# ETHERNET_STM32.net
KiCad netlist of a schematic drawn in Altium Designer
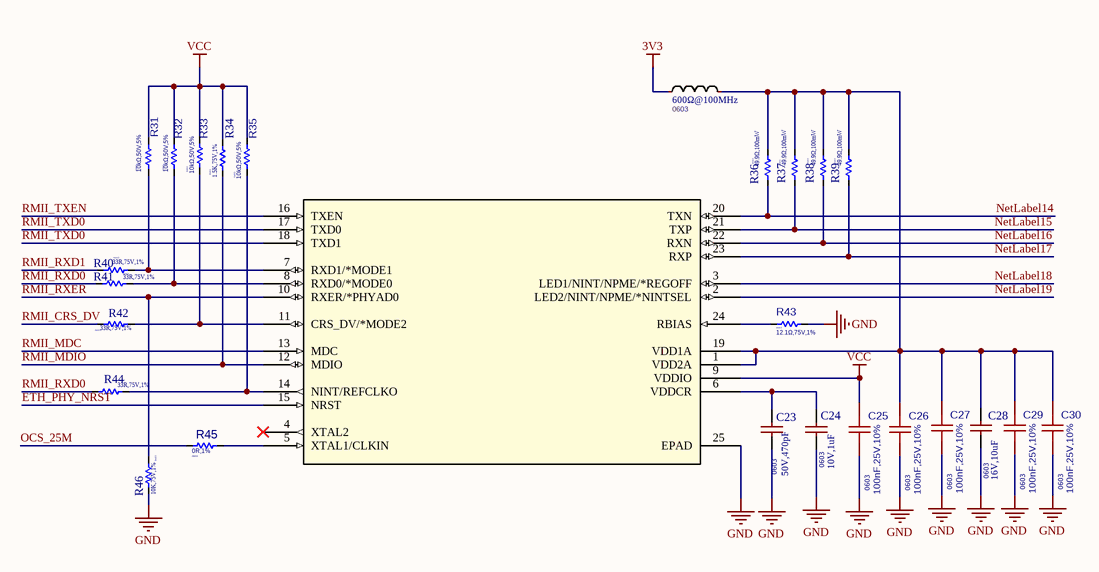
[diagram p0: ETHERNET_STM32.SchDoc]

(export (version "E")
  (design (tool "Eeschema 10.0.6"))
  (components
    (comp (ref "C23")
      (value "50V,470pF")
      (footprint "c-0603")
      (description "50V 470pF X7R ±10% 0603 Multilayer Ceramic Capacitors MLCC - SMD/SMT ROHS")
      (fields
        (field (name "MANUFACTURER") "FH")
        (field (name "MPN") "CL10B471KB8NNNC")
        (field (name "PACKAGE") "0603")
      )
      (libsource (lib "RCL") (part "CL10B471KB8NNNC"))
    )
    (comp (ref "C24")
      (value "10V,1uF")
      (footprint "CAPC1608X90N")
      (description "10V 1uF X5R ±10% 0603 Multilayer Ceramic Capacitors MLCC - SMD/SMT ROHS")
      (fields
        (field (name "MANUFACTURER") "SAMSUNG")
        (field (name "MPN") "CL10A105KP8NNNC")
        (field (name "PACKAGE") "0603")
      )
      (libsource (lib "RCL") (part "CL10A105KP8NNNC"))
    )
    (comp (ref "C25")
      (value "100nF,25V,10%")
      (footprint "C0603")
      (description "25V 100nF X7R ±10% 0603 Multilayer Ceramic Capacitors MLCC - SMD/SMT ROHS")
      (fields
        (field (name "MANUFACTURER") "SAMSUNG")
        (field (name "MPN") "CL10B104KA8NNNC")
        (field (name "PACKAGE") "0603")
      )
      (libsource (lib "RCL") (part "CL10B104KA8NNNC"))
    )
    (comp (ref "C26")
      (value "100nF,25V,10%")
      (footprint "C0603")
      (description "25V 100nF X7R ±10% 0603 Multilayer Ceramic Capacitors MLCC - SMD/SMT ROHS")
      (fields
        (field (name "MANUFACTURER") "SAMSUNG")
        (field (name "MPN") "CL10B104KA8NNNC")
        (field (name "PACKAGE") "0603")
      )
      (libsource (lib "RCL") (part "CL10B104KA8NNNC"))
    )
    (comp (ref "C27")
      (value "100nF,25V,10%")
      (footprint "C0603")
      (description "25V 100nF X7R ±10% 0603 Multilayer Ceramic Capacitors MLCC - SMD/SMT ROHS")
      (fields
        (field (name "MANUFACTURER") "SAMSUNG")
        (field (name "MPN") "CL10B104KA8NNNC")
        (field (name "PACKAGE") "0603")
      )
      (libsource (lib "RCL") (part "CL10B104KA8NNNC"))
    )
    (comp (ref "C28")
      (value "16V,10uF")
      (footprint "CAPC1608X90N")
      (description "16V 10uF Y5V ±20% 0603 Multilayer Ceramic Capacitors MLCC - SMD/SMT ROHS")
      (fields
        (field (name "MANUFACTURER") "KEMET")
        (field (name "MPN") "CC0603KRX7R9BB104")
        (field (name "PACKAGE") "0603")
      )
      (libsource (lib "RCL") (part "0603F106M160NT"))
    )
    (comp (ref "C29")
      (value "100nF,25V,10%")
      (footprint "C0603")
      (description "25V 100nF X7R ±10% 0603 Multilayer Ceramic Capacitors MLCC - SMD/SMT ROHS")
      (fields
        (field (name "MANUFACTURER") "SAMSUNG")
        (field (name "MPN") "CL10B104KA8NNNC")
        (field (name "PACKAGE") "0603")
      )
      (libsource (lib "RCL") (part "CL10B104KA8NNNC"))
    )
    (comp (ref "C30")
      (value "100nF,25V,10%")
      (footprint "C0603")
      (description "25V 100nF X7R ±10% 0603 Multilayer Ceramic Capacitors MLCC - SMD/SMT ROHS")
      (fields
        (field (name "MANUFACTURER") "SAMSUNG")
        (field (name "MPN") "CL10B104KA8NNNC")
        (field (name "PACKAGE") "0603")
      )
      (libsource (lib "RCL") (part "CL10B104KA8NNNC"))
    )
    (comp (ref "R31")
      (value "10kΩ,50V,5%")
      (footprint "R0402")
      (description "62.5mW Thick Film Resistors 50V ±100ppm/℃ ±5% 10kΩ 0402 Chip Resistor - Surface Mount ROHS")
      (fields
        (field (name "MANUFACTURER") "YAGEO")
        (field (name "MPN") "RC0402JR-0710KL")
        (field (name "PACKAGE") "0402")
      )
      (libsource (lib "RCL") (part "RC0402JR-0710KL"))
    )
    (comp (ref "R32")
      (value "10kΩ,50V,5%")
      (footprint "R0402")
      (description "62.5mW Thick Film Resistors 50V ±100ppm/℃ ±5% 10kΩ 0402 Chip Resistor - Surface Mount ROHS")
      (fields
        (field (name "MANUFACTURER") "YAGEO")
        (field (name "MPN") "RC0402JR-0710KL")
        (field (name "PACKAGE") "0402")
      )
      (libsource (lib "RCL") (part "RC0402JR-0710KL"))
    )
    (comp (ref "R33")
      (value "10kΩ,50V,5%")
      (footprint "R0402")
      (description "62.5mW Thick Film Resistors 50V ±100ppm/℃ ±5% 10kΩ 0402 Chip Resistor - Surface Mount ROHS")
      (fields
        (field (name "MANUFACTURER") "YAGEO")
        (field (name "MPN") "RC0402JR-0710KL")
        (field (name "PACKAGE") "0402")
      )
      (libsource (lib "RCL") (part "RC0402JR-0710KL"))
    )
    (comp (ref "R34")
      (value "1.5K,75V,1%")
      (footprint "R0603")
      (description "100mW Thick Film Resistors 75V ±100ppm/℃ ±1% 1.5kΩ 0603 Chip Resistor - Surface Mount ROHS")
      (fields
        (field (name "MANUFACTURER") "Yageo")
        (field (name "MPN") "RC0603FR-071K5L")
        (field (name "PACKAGE") "0603")
      )
      (libsource (lib "RCL") (part "RC0603FR-071K5L"))
    )
    (comp (ref "R35")
      (value "10kΩ,50V,5%")
      (footprint "R0402")
      (description "62.5mW Thick Film Resistors 50V ±100ppm/℃ ±5% 10kΩ 0402 Chip Resistor - Surface Mount ROHS")
      (fields
        (field (name "MANUFACTURER") "YAGEO")
        (field (name "MPN") "RC0402JR-0710KL")
        (field (name "PACKAGE") "0402")
      )
      (libsource (lib "RCL") (part "RC0402JR-0710KL"))
    )
    (comp (ref "R36")
      (value "49.9Ω,100mW")
      (footprint "R0603")
      (description "100mW Thick Film Resistors ±100ppm/℃ ±1% 49.9Ω 0603 Chip Resistor - Surface Mount ROHS")
      (fields
        (field (name "MANUFACTURER") "Panasonic")
        (field (name "MPN") "ERJ-3EKF49R9V")
        (field (name "PACKAGE") "0603")
      )
      (libsource (lib "RCL") (part "ERJ-3EKF49R9V"))
    )
    (comp (ref "R37")
      (value "49.9Ω,100mW")
      (footprint "R0603")
      (description "100mW Thick Film Resistors ±100ppm/℃ ±1% 49.9Ω 0603 Chip Resistor - Surface Mount ROHS")
      (fields
        (field (name "MANUFACTURER") "Panasonic")
        (field (name "MPN") "ERJ-3EKF49R9V")
        (field (name "PACKAGE") "0603")
      )
      (libsource (lib "RCL") (part "ERJ-3EKF49R9V"))
    )
    (comp (ref "R38")
      (value "49.9Ω,100mW")
      (footprint "R0603")
      (description "100mW Thick Film Resistors ±100ppm/℃ ±1% 49.9Ω 0603 Chip Resistor - Surface Mount ROHS")
      (fields
        (field (name "MANUFACTURER") "Panasonic")
        (field (name "MPN") "ERJ-3EKF49R9V")
        (field (name "PACKAGE") "0603")
      )
      (libsource (lib "RCL") (part "ERJ-3EKF49R9V"))
    )
    (comp (ref "R39")
      (value "49.9Ω,100mW")
      (footprint "R0603")
      (description "100mW Thick Film Resistors ±100ppm/℃ ±1% 49.9Ω 0603 Chip Resistor - Surface Mount ROHS")
      (fields
        (field (name "MANUFACTURER") "Panasonic")
        (field (name "MPN") "ERJ-3EKF49R9V")
        (field (name "PACKAGE") "0603")
      )
      (libsource (lib "RCL") (part "ERJ-3EKF49R9V"))
    )
    (comp (ref "R40")
      (value "33R,75V,1%")
      (footprint "R0603")
      (description "100mW Thick Film Resistors 75V ±100ppm/℃ ±1% 270Ω 0603 Chip Resistor - Surface Mount ROHS")
      (fields
        (field (name "MANUFACTURER") "Yageo")
        (field (name "MPN") "RC0603FR-0733RL")
        (field (name "PACKAGE") "0603")
      )
      (libsource (lib "RCL") (part "RC0603FR-0733RL"))
    )
    (comp (ref "R41")
      (value "33R,75V,1%")
      (footprint "R0603")
      (description "100mW Thick Film Resistors 75V ±100ppm/℃ ±1% 270Ω 0603 Chip Resistor - Surface Mount ROHS")
      (fields
        (field (name "MANUFACTURER") "Yageo")
        (field (name "MPN") "RC0603FR-0733RL")
        (field (name "PACKAGE") "0603")
      )
      (libsource (lib "RCL") (part "RC0603FR-0733RL"))
    )
    (comp (ref "R42")
      (value "33R,75V,1%")
      (footprint "R0603")
      (description "100mW Thick Film Resistors 75V ±100ppm/℃ ±1% 270Ω 0603 Chip Resistor - Surface Mount ROHS")
      (fields
        (field (name "MANUFACTURER") "Yageo")
        (field (name "MPN") "RC0603FR-0733RL")
        (field (name "PACKAGE") "0603")
      )
      (libsource (lib "RCL") (part "RC0603FR-0733RL"))
    )
    (comp (ref "R43")
      (value "12.1Ω,75V,1%")
      (footprint "R0603")
      (description "100mW Thick Film Resistors 75V ±100ppm/℃ ±1% 12.1kΩ 0603 Chip Resistor - Surface Mount ROHS")
      (fields
        (field (name "MPN") "RC0603FR-0712K1L")
        (field (name "MANUFACTURER") "YAGEO")
        (field (name "PACKAGE") "0603")
      )
      (libsource (lib "RCL") (part "RC0603FR-0712K1L"))
    )
    (comp (ref "R44")
      (value "33R,75V,1%")
      (footprint "R0603")
      (description "100mW Thick Film Resistors 75V ±100ppm/℃ ±1% 270Ω 0603 Chip Resistor - Surface Mount ROHS")
      (fields
        (field (name "MANUFACTURER") "Yageo")
        (field (name "MPN") "RC0603FR-0733RL")
        (field (name "PACKAGE") "0603")
      )
      (libsource (lib "RCL") (part "RC0603FR-0733RL"))
    )
    (comp (ref "R45")
      (value "0R,1%")
      (footprint "R0603")
      (description "RES SMD 0 OHM JUMPER 1/10W 0603")
      (fields
        (field (name "MANUFACTURER") "YAGEO")
        (field (name "MPN") "AC0603FR-070RL")
        (field (name "PACKAGE") "0603")
      )
      (libsource (lib "RCL") (part "AC0603FR-070RL"))
    )
    (comp (ref "R46")
      (value "10K,75V,1%")
      (footprint "R0603")
      (description "100mW Thick Film Resistors ±100ppm/℃ ±1% 10kΩ 0603 Chip Resistor - Surface Mount ROHS")
      (fields
        (field (name "MPN") "0603WAF1002T5E")
        (field (name "MANUFACTURER") "UNI-ROYAL(Uniroyal Elec)")
        (field (name "PACKAGE") "0603")
      )
      (libsource (lib "RCL") (part "0603WAF1002T5E"))
    )
    (comp (ref "U4")
      (value "600Ω@100MHz")
      (footprint "L-0603")
      (description "380mΩ ±25% 600Ω@100MHz 0603 Ferrite Beads ROHS")
      (fields
        (field (name "MANUFACTURER") "muRata")
        (field (name "MPN") "BLM18AG601SN1D")
        (field (name "PACKAGE") "0603")
      )
      (libsource (lib "RCL") (part "BLM18AG601SN1D"))
    )
    (comp (ref "U5")
      (value "LAN8742A-CZ-TR")
      (footprint "QFN-24-EP(4x4)")
      (description "QFN-24-EP(4x4) Ethernet ICs ROHS")
      (fields (field (name "MANUFACTURER") "MICROCHIP(美国微芯)"))
      (libsource (lib "IC") (part "LAN8742A-CZ-TR"))
    )
  )
  (nets
    (net (code "1") (name "/ETH_PHY_NRST") (class "Default")
      (node (ref "U5") (pin "15") (pinfunction "NRST_15") (pintype "input"))
    )
    (net (code "2") (name "/NetLabel14") (class "Default")
      (node (ref "R36") (pin "1") (pinfunction "1_1") (pintype "passive"))
      (node (ref "U5") (pin "20") (pinfunction "TXN_20") (pintype "bidirectional"))
    )
    (net (code "3") (name "/NetLabel15") (class "Default")
      (node (ref "R37") (pin "1") (pinfunction "1_1") (pintype "passive"))
      (node (ref "U5") (pin "21") (pinfunction "TXP_21") (pintype "bidirectional"))
    )
    (net (code "4") (name "/NetLabel16") (class "Default")
      (node (ref "R38") (pin "1") (pinfunction "1_1") (pintype "passive"))
      (node (ref "U5") (pin "22") (pinfunction "RXN_22") (pintype "bidirectional"))
    )
    (net (code "5") (name "/NetLabel17") (class "Default")
      (node (ref "R39") (pin "1") (pinfunction "1_1") (pintype "passive"))
      (node (ref "U5") (pin "23") (pinfunction "RXP_23") (pintype "bidirectional"))
    )
    (net (code "6") (name "/NetLabel18") (class "Default")
      (node (ref "U5") (pin "3") (pinfunction "LED1/NINT/NPME/*REGOFF_3") (pintype "bidirectional"))
    )
    (net (code "7") (name "/NetLabel19") (class "Default")
      (node (ref "U5") (pin "2") (pinfunction "LED2/NINT/NPME/*NINTSEL_2") (pintype "bidirectional"))
    )
    (net (code "8") (name "/OCS_25M") (class "Default")
      (node (ref "R45") (pin "1") (pinfunction "1_1") (pintype "passive"))
    )
    (net (code "9") (name "/RMII_CRS_DV") (class "Default")
      (node (ref "R42") (pin "1") (pinfunction "1_1") (pintype "passive"))
    )
    (net (code "10") (name "/RMII_MDC") (class "Default")
      (node (ref "U5") (pin "13") (pinfunction "MDC_13") (pintype "input"))
    )
    (net (code "11") (name "/RMII_MDIO") (class "Default")
      (node (ref "R34") (pin "1") (pinfunction "1_1") (pintype "passive"))
      (node (ref "U5") (pin "12") (pinfunction "MDIO_12") (pintype "bidirectional"))
    )
    (net (code "12") (name "/RMII_RXD0") (class "Default")
      (node (ref "R41") (pin "1") (pinfunction "1_1") (pintype "passive"))
      (node (ref "R44") (pin "1") (pinfunction "1_1") (pintype "passive"))
    )
    (net (code "13") (name "/RMII_RXD1") (class "Default")
      (node (ref "R40") (pin "1") (pinfunction "1_1") (pintype "passive"))
    )
    (net (code "14") (name "/RMII_RXER") (class "Default")
      (node (ref "R46") (pin "2") (pinfunction "2_2") (pintype "passive"))
      (node (ref "U5") (pin "10") (pinfunction "RXER/*PHYAD0_10") (pintype "bidirectional"))
    )
    (net (code "15") (name "/RMII_TXD0") (class "Default")
      (node (ref "U5") (pin "17") (pinfunction "TXD0_17") (pintype "input"))
      (node (ref "U5") (pin "18") (pinfunction "TXD1_18") (pintype "input"))
    )
    (net (code "16") (name "/RMII_TXEN") (class "Default")
      (node (ref "U5") (pin "16") (pinfunction "TXEN_16") (pintype "input"))
    )
    (net (code "17") (name "3V3") (class "Default")
      (node (ref "U4") (pin "1") (pinfunction "1_1") (pintype "passive"))
    )
    (net (code "18") (name "GND") (class "Default")
      (node (ref "C23") (pin "1") (pinfunction "1_1") (pintype "passive"))
      (node (ref "C24") (pin "1") (pinfunction "1_1") (pintype "passive"))
      (node (ref "C25") (pin "1") (pinfunction "1_1") (pintype "passive"))
      (node (ref "C26") (pin "1") (pinfunction "1_1") (pintype "passive"))
      (node (ref "C27") (pin "1") (pinfunction "1_1") (pintype "passive"))
      (node (ref "C28") (pin "1") (pinfunction "1_1") (pintype "passive"))
      (node (ref "C29") (pin "1") (pinfunction "1_1") (pintype "passive"))
      (node (ref "C30") (pin "1") (pinfunction "1_1") (pintype "passive"))
      (node (ref "R43") (pin "2") (pinfunction "2_2") (pintype "passive"))
      (node (ref "R46") (pin "1") (pinfunction "1_1") (pintype "passive"))
      (node (ref "U5") (pin "25") (pinfunction "EPAD_25") (pintype "passive"))
    )
    (net (code "19") (name "Net-(U5-CRS_DV{slash}*MODE2)") (class "Default")
      (node (ref "R33") (pin "1") (pinfunction "1_1") (pintype "passive"))
      (node (ref "R42") (pin "2") (pinfunction "2_2") (pintype "passive"))
      (node (ref "U5") (pin "11") (pinfunction "CRS_DV/*MODE2_11") (pintype "bidirectional"))
    )
    (net (code "20") (name "Net-(U5-NINT{slash}REFCLKO)") (class "Default")
      (node (ref "R35") (pin "1") (pinfunction "1_1") (pintype "passive"))
      (node (ref "R44") (pin "2") (pinfunction "2_2") (pintype "passive"))
      (node (ref "U5") (pin "14") (pinfunction "NINT/REFCLKO_14") (pintype "output"))
    )
    (net (code "21") (name "Net-(U5-RBIAS)") (class "Default")
      (node (ref "R43") (pin "1") (pinfunction "1_1") (pintype "passive"))
      (node (ref "U5") (pin "24") (pinfunction "RBIAS_24") (pintype "input"))
    )
    (net (code "22") (name "Net-(U5-RXD0{slash}*MODE0)") (class "Default")
      (node (ref "R32") (pin "1") (pinfunction "1_1") (pintype "passive"))
      (node (ref "R41") (pin "2") (pinfunction "2_2") (pintype "passive"))
      (node (ref "U5") (pin "8") (pinfunction "RXD0/*MODE0_8") (pintype "bidirectional"))
    )
    (net (code "23") (name "Net-(U5-RXD1{slash}*MODE1)") (class "Default")
      (node (ref "R31") (pin "1") (pinfunction "1_1") (pintype "passive"))
      (node (ref "R40") (pin "2") (pinfunction "2_2") (pintype "passive"))
      (node (ref "U5") (pin "7") (pinfunction "RXD1/*MODE1_7") (pintype "bidirectional"))
    )
    (net (code "24") (name "Net-(U5-VDD1A)") (class "Default")
      (node (ref "C26") (pin "2") (pinfunction "2_2") (pintype "passive"))
      (node (ref "C27") (pin "2") (pinfunction "2_2") (pintype "passive"))
      (node (ref "C28") (pin "2") (pinfunction "2_2") (pintype "passive"))
      (node (ref "C29") (pin "2") (pinfunction "2_2") (pintype "passive"))
      (node (ref "C30") (pin "2") (pinfunction "2_2") (pintype "passive"))
      (node (ref "R36") (pin "2") (pinfunction "2_2") (pintype "passive"))
      (node (ref "R37") (pin "2") (pinfunction "2_2") (pintype "passive"))
      (node (ref "R38") (pin "2") (pinfunction "2_2") (pintype "passive"))
      (node (ref "R39") (pin "2") (pinfunction "2_2") (pintype "passive"))
      (node (ref "U4") (pin "2") (pinfunction "2_2") (pintype "passive"))
      (node (ref "U5") (pin "1") (pinfunction "VDD2A_1") (pintype "power_in"))
      (node (ref "U5") (pin "19") (pinfunction "VDD1A_19") (pintype "power_in"))
    )
    (net (code "25") (name "Net-(U5-VDDCR)") (class "Default")
      (node (ref "C23") (pin "2") (pinfunction "2_2") (pintype "passive"))
      (node (ref "C24") (pin "2") (pinfunction "2_2") (pintype "passive"))
      (node (ref "U5") (pin "6") (pinfunction "VDDCR_6") (pintype "power_in"))
    )
    (net (code "26") (name "Net-(U5-XTAL1{slash}CLKIN)") (class "Default")
      (node (ref "R45") (pin "2") (pinfunction "2_2") (pintype "passive"))
      (node (ref "U5") (pin "5") (pinfunction "XTAL1/CLKIN_5") (pintype "input"))
    )
    (net (code "27") (name "VCC") (class "Default")
      (node (ref "C25") (pin "2") (pinfunction "2_2") (pintype "passive"))
      (node (ref "R31") (pin "2") (pinfunction "2_2") (pintype "passive"))
      (node (ref "R32") (pin "2") (pinfunction "2_2") (pintype "passive"))
      (node (ref "R33") (pin "2") (pinfunction "2_2") (pintype "passive"))
      (node (ref "R34") (pin "2") (pinfunction "2_2") (pintype "passive"))
      (node (ref "R35") (pin "2") (pinfunction "2_2") (pintype "passive"))
      (node (ref "U5") (pin "9") (pinfunction "VDDIO_9") (pintype "power_in"))
    )
    (net (code "28") (name "unconnected-(U5-XTAL2-Pad4)") (class "Default")
      (node (ref "U5") (pin "4") (pinfunction "XTAL2_4") (pintype "output+no_connect"))
    )
  )
)
